# SenseEnable.net
KiCad netlist of a schematic drawn in Altium Designer
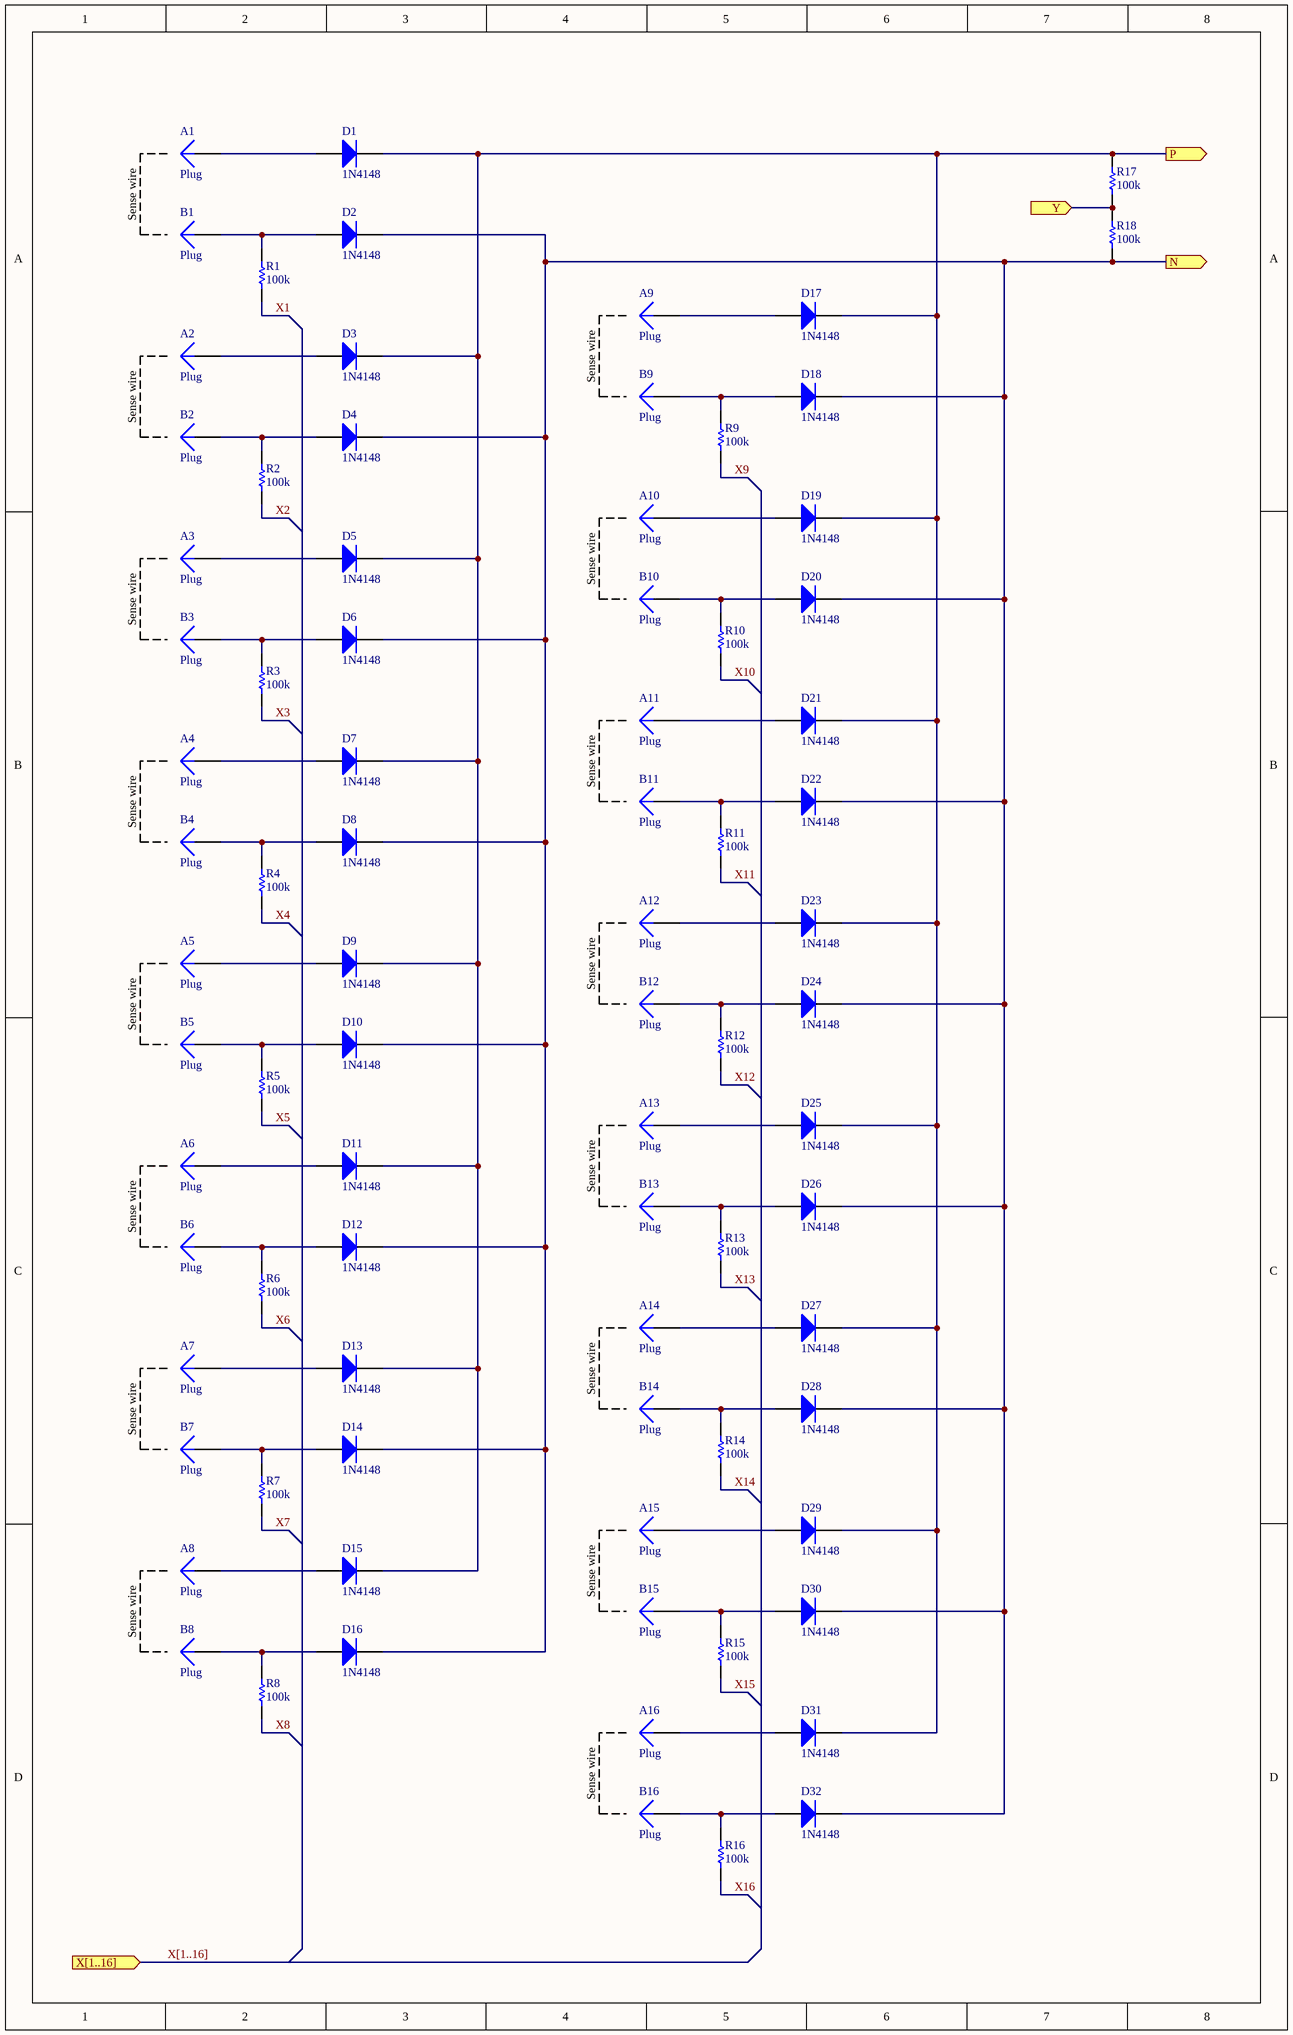
[diagram p0: SenseEnable.SchDoc]

(export (version "E")
  (design (tool "Eeschema 10.0.6"))
  (components
    (comp (ref "A1")
      (value "Plug")
      (footprint "PIN1")
      (fields (field (name "PUBLISHER") "Altium Limited"))
      (libsource (lib "Miscellaneous Connectors") (part "Plug"))
    )
    (comp (ref "A2")
      (value "Plug")
      (footprint "PIN1")
      (fields (field (name "PUBLISHER") "Altium Limited"))
      (libsource (lib "Miscellaneous Connectors") (part "Plug"))
    )
    (comp (ref "A3")
      (value "Plug")
      (footprint "PIN1")
      (fields (field (name "PUBLISHER") "Altium Limited"))
      (libsource (lib "Miscellaneous Connectors") (part "Plug"))
    )
    (comp (ref "A4")
      (value "Plug")
      (footprint "PIN1")
      (fields (field (name "PUBLISHER") "Altium Limited"))
      (libsource (lib "Miscellaneous Connectors") (part "Plug"))
    )
    (comp (ref "A5")
      (value "Plug")
      (footprint "PIN1")
      (fields (field (name "PUBLISHER") "Altium Limited"))
      (libsource (lib "Miscellaneous Connectors") (part "Plug"))
    )
    (comp (ref "A6")
      (value "Plug")
      (footprint "PIN1")
      (fields (field (name "PUBLISHER") "Altium Limited"))
      (libsource (lib "Miscellaneous Connectors") (part "Plug"))
    )
    (comp (ref "A7")
      (value "Plug")
      (footprint "PIN1")
      (fields (field (name "PUBLISHER") "Altium Limited"))
      (libsource (lib "Miscellaneous Connectors") (part "Plug"))
    )
    (comp (ref "A8")
      (value "Plug")
      (footprint "PIN1")
      (fields (field (name "PUBLISHER") "Altium Limited"))
      (libsource (lib "Miscellaneous Connectors") (part "Plug"))
    )
    (comp (ref "A9")
      (value "Plug")
      (footprint "PIN1")
      (fields (field (name "PUBLISHER") "Altium Limited"))
      (libsource (lib "Miscellaneous Connectors") (part "Plug"))
    )
    (comp (ref "A10")
      (value "Plug")
      (footprint "PIN1")
      (fields (field (name "PUBLISHER") "Altium Limited"))
      (libsource (lib "Miscellaneous Connectors") (part "Plug"))
    )
    (comp (ref "A11")
      (value "Plug")
      (footprint "PIN1")
      (fields (field (name "PUBLISHER") "Altium Limited"))
      (libsource (lib "Miscellaneous Connectors") (part "Plug"))
    )
    (comp (ref "A12")
      (value "Plug")
      (footprint "PIN1")
      (fields (field (name "PUBLISHER") "Altium Limited"))
      (libsource (lib "Miscellaneous Connectors") (part "Plug"))
    )
    (comp (ref "A13")
      (value "Plug")
      (footprint "PIN1")
      (fields (field (name "PUBLISHER") "Altium Limited"))
      (libsource (lib "Miscellaneous Connectors") (part "Plug"))
    )
    (comp (ref "A14")
      (value "Plug")
      (footprint "PIN1")
      (fields (field (name "PUBLISHER") "Altium Limited"))
      (libsource (lib "Miscellaneous Connectors") (part "Plug"))
    )
    (comp (ref "A15")
      (value "Plug")
      (footprint "PIN1")
      (fields (field (name "PUBLISHER") "Altium Limited"))
      (libsource (lib "Miscellaneous Connectors") (part "Plug"))
    )
    (comp (ref "A16")
      (value "Plug")
      (footprint "PIN1")
      (fields (field (name "PUBLISHER") "Altium Limited"))
      (libsource (lib "Miscellaneous Connectors") (part "Plug"))
    )
    (comp (ref "B1")
      (value "Plug")
      (footprint "PIN1")
      (fields (field (name "PUBLISHER") "Altium Limited"))
      (libsource (lib "Miscellaneous Connectors") (part "Plug"))
    )
    (comp (ref "B2")
      (value "Plug")
      (footprint "PIN1")
      (fields (field (name "PUBLISHER") "Altium Limited"))
      (libsource (lib "Miscellaneous Connectors") (part "Plug"))
    )
    (comp (ref "B3")
      (value "Plug")
      (footprint "PIN1")
      (fields (field (name "PUBLISHER") "Altium Limited"))
      (libsource (lib "Miscellaneous Connectors") (part "Plug"))
    )
    (comp (ref "B4")
      (value "Plug")
      (footprint "PIN1")
      (fields (field (name "PUBLISHER") "Altium Limited"))
      (libsource (lib "Miscellaneous Connectors") (part "Plug"))
    )
    (comp (ref "B5")
      (value "Plug")
      (footprint "PIN1")
      (fields (field (name "PUBLISHER") "Altium Limited"))
      (libsource (lib "Miscellaneous Connectors") (part "Plug"))
    )
    (comp (ref "B6")
      (value "Plug")
      (footprint "PIN1")
      (fields (field (name "PUBLISHER") "Altium Limited"))
      (libsource (lib "Miscellaneous Connectors") (part "Plug"))
    )
    (comp (ref "B7")
      (value "Plug")
      (footprint "PIN1")
      (fields (field (name "PUBLISHER") "Altium Limited"))
      (libsource (lib "Miscellaneous Connectors") (part "Plug"))
    )
    (comp (ref "B8")
      (value "Plug")
      (footprint "PIN1")
      (fields (field (name "PUBLISHER") "Altium Limited"))
      (libsource (lib "Miscellaneous Connectors") (part "Plug"))
    )
    (comp (ref "B9")
      (value "Plug")
      (footprint "PIN1")
      (fields (field (name "PUBLISHER") "Altium Limited"))
      (libsource (lib "Miscellaneous Connectors") (part "Plug"))
    )
    (comp (ref "B10")
      (value "Plug")
      (footprint "PIN1")
      (fields (field (name "PUBLISHER") "Altium Limited"))
      (libsource (lib "Miscellaneous Connectors") (part "Plug"))
    )
    (comp (ref "B11")
      (value "Plug")
      (footprint "PIN1")
      (fields (field (name "PUBLISHER") "Altium Limited"))
      (libsource (lib "Miscellaneous Connectors") (part "Plug"))
    )
    (comp (ref "B12")
      (value "Plug")
      (footprint "PIN1")
      (fields (field (name "PUBLISHER") "Altium Limited"))
      (libsource (lib "Miscellaneous Connectors") (part "Plug"))
    )
    (comp (ref "B13")
      (value "Plug")
      (footprint "PIN1")
      (fields (field (name "PUBLISHER") "Altium Limited"))
      (libsource (lib "Miscellaneous Connectors") (part "Plug"))
    )
    (comp (ref "B14")
      (value "Plug")
      (footprint "PIN1")
      (fields (field (name "PUBLISHER") "Altium Limited"))
      (libsource (lib "Miscellaneous Connectors") (part "Plug"))
    )
    (comp (ref "B15")
      (value "Plug")
      (footprint "PIN1")
      (fields (field (name "PUBLISHER") "Altium Limited"))
      (libsource (lib "Miscellaneous Connectors") (part "Plug"))
    )
    (comp (ref "B16")
      (value "Plug")
      (footprint "PIN1")
      (fields (field (name "PUBLISHER") "Altium Limited"))
      (libsource (lib "Miscellaneous Connectors") (part "Plug"))
    )
    (comp (ref "D1")
      (value "1N4148")
      (footprint "DO-35")
      (description "High Conductance Fast Diode")
      (fields (field (name "PUBLISHER") "Altium Limited"))
      (libsource (lib "Miscellaneous Devices") (part "Diode 1N4148"))
    )
    (comp (ref "D2")
      (value "1N4148")
      (footprint "DO-35")
      (description "High Conductance Fast Diode")
      (fields (field (name "PUBLISHER") "Altium Limited"))
      (libsource (lib "Miscellaneous Devices") (part "Diode 1N4148"))
    )
    (comp (ref "D3")
      (value "1N4148")
      (footprint "DO-35")
      (description "High Conductance Fast Diode")
      (fields (field (name "PUBLISHER") "Altium Limited"))
      (libsource (lib "Miscellaneous Devices") (part "Diode 1N4148"))
    )
    (comp (ref "D4")
      (value "1N4148")
      (footprint "DO-35")
      (description "High Conductance Fast Diode")
      (fields (field (name "PUBLISHER") "Altium Limited"))
      (libsource (lib "Miscellaneous Devices") (part "Diode 1N4148"))
    )
    (comp (ref "D5")
      (value "1N4148")
      (footprint "DO-35")
      (description "High Conductance Fast Diode")
      (fields (field (name "PUBLISHER") "Altium Limited"))
      (libsource (lib "Miscellaneous Devices") (part "Diode 1N4148"))
    )
    (comp (ref "D6")
      (value "1N4148")
      (footprint "DO-35")
      (description "High Conductance Fast Diode")
      (fields (field (name "PUBLISHER") "Altium Limited"))
      (libsource (lib "Miscellaneous Devices") (part "Diode 1N4148"))
    )
    (comp (ref "D7")
      (value "1N4148")
      (footprint "DO-35")
      (description "High Conductance Fast Diode")
      (fields (field (name "PUBLISHER") "Altium Limited"))
      (libsource (lib "Miscellaneous Devices") (part "Diode 1N4148"))
    )
    (comp (ref "D8")
      (value "1N4148")
      (footprint "DO-35")
      (description "High Conductance Fast Diode")
      (fields (field (name "PUBLISHER") "Altium Limited"))
      (libsource (lib "Miscellaneous Devices") (part "Diode 1N4148"))
    )
    (comp (ref "D9")
      (value "1N4148")
      (footprint "DO-35")
      (description "High Conductance Fast Diode")
      (fields (field (name "PUBLISHER") "Altium Limited"))
      (libsource (lib "Miscellaneous Devices") (part "Diode 1N4148"))
    )
    (comp (ref "D10")
      (value "1N4148")
      (footprint "DO-35")
      (description "High Conductance Fast Diode")
      (fields (field (name "PUBLISHER") "Altium Limited"))
      (libsource (lib "Miscellaneous Devices") (part "Diode 1N4148"))
    )
    (comp (ref "D11")
      (value "1N4148")
      (footprint "DO-35")
      (description "High Conductance Fast Diode")
      (fields (field (name "PUBLISHER") "Altium Limited"))
      (libsource (lib "Miscellaneous Devices") (part "Diode 1N4148"))
    )
    (comp (ref "D12")
      (value "1N4148")
      (footprint "DO-35")
      (description "High Conductance Fast Diode")
      (fields (field (name "PUBLISHER") "Altium Limited"))
      (libsource (lib "Miscellaneous Devices") (part "Diode 1N4148"))
    )
    (comp (ref "D13")
      (value "1N4148")
      (footprint "DO-35")
      (description "High Conductance Fast Diode")
      (fields (field (name "PUBLISHER") "Altium Limited"))
      (libsource (lib "Miscellaneous Devices") (part "Diode 1N4148"))
    )
    (comp (ref "D14")
      (value "1N4148")
      (footprint "DO-35")
      (description "High Conductance Fast Diode")
      (fields (field (name "PUBLISHER") "Altium Limited"))
      (libsource (lib "Miscellaneous Devices") (part "Diode 1N4148"))
    )
    (comp (ref "D15")
      (value "1N4148")
      (footprint "DO-35")
      (description "High Conductance Fast Diode")
      (fields (field (name "PUBLISHER") "Altium Limited"))
      (libsource (lib "Miscellaneous Devices") (part "Diode 1N4148"))
    )
    (comp (ref "D16")
      (value "1N4148")
      (footprint "DO-35")
      (description "High Conductance Fast Diode")
      (fields (field (name "PUBLISHER") "Altium Limited"))
      (libsource (lib "Miscellaneous Devices") (part "Diode 1N4148"))
    )
    (comp (ref "D17")
      (value "1N4148")
      (footprint "DO-35")
      (description "High Conductance Fast Diode")
      (fields (field (name "PUBLISHER") "Altium Limited"))
      (libsource (lib "Miscellaneous Devices") (part "Diode 1N4148"))
    )
    (comp (ref "D18")
      (value "1N4148")
      (footprint "DO-35")
      (description "High Conductance Fast Diode")
      (fields (field (name "PUBLISHER") "Altium Limited"))
      (libsource (lib "Miscellaneous Devices") (part "Diode 1N4148"))
    )
    (comp (ref "D19")
      (value "1N4148")
      (footprint "DO-35")
      (description "High Conductance Fast Diode")
      (fields (field (name "PUBLISHER") "Altium Limited"))
      (libsource (lib "Miscellaneous Devices") (part "Diode 1N4148"))
    )
    (comp (ref "D20")
      (value "1N4148")
      (footprint "DO-35")
      (description "High Conductance Fast Diode")
      (fields (field (name "PUBLISHER") "Altium Limited"))
      (libsource (lib "Miscellaneous Devices") (part "Diode 1N4148"))
    )
    (comp (ref "D21")
      (value "1N4148")
      (footprint "DO-35")
      (description "High Conductance Fast Diode")
      (fields (field (name "PUBLISHER") "Altium Limited"))
      (libsource (lib "Miscellaneous Devices") (part "Diode 1N4148"))
    )
    (comp (ref "D22")
      (value "1N4148")
      (footprint "DO-35")
      (description "High Conductance Fast Diode")
      (fields (field (name "PUBLISHER") "Altium Limited"))
      (libsource (lib "Miscellaneous Devices") (part "Diode 1N4148"))
    )
    (comp (ref "D23")
      (value "1N4148")
      (footprint "DO-35")
      (description "High Conductance Fast Diode")
      (fields (field (name "PUBLISHER") "Altium Limited"))
      (libsource (lib "Miscellaneous Devices") (part "Diode 1N4148"))
    )
    (comp (ref "D24")
      (value "1N4148")
      (footprint "DO-35")
      (description "High Conductance Fast Diode")
      (fields (field (name "PUBLISHER") "Altium Limited"))
      (libsource (lib "Miscellaneous Devices") (part "Diode 1N4148"))
    )
    (comp (ref "D25")
      (value "1N4148")
      (footprint "DO-35")
      (description "High Conductance Fast Diode")
      (fields (field (name "PUBLISHER") "Altium Limited"))
      (libsource (lib "Miscellaneous Devices") (part "Diode 1N4148"))
    )
    (comp (ref "D26")
      (value "1N4148")
      (footprint "DO-35")
      (description "High Conductance Fast Diode")
      (fields (field (name "PUBLISHER") "Altium Limited"))
      (libsource (lib "Miscellaneous Devices") (part "Diode 1N4148"))
    )
    (comp (ref "D27")
      (value "1N4148")
      (footprint "DO-35")
      (description "High Conductance Fast Diode")
      (fields (field (name "PUBLISHER") "Altium Limited"))
      (libsource (lib "Miscellaneous Devices") (part "Diode 1N4148"))
    )
    (comp (ref "D28")
      (value "1N4148")
      (footprint "DO-35")
      (description "High Conductance Fast Diode")
      (fields (field (name "PUBLISHER") "Altium Limited"))
      (libsource (lib "Miscellaneous Devices") (part "Diode 1N4148"))
    )
    (comp (ref "D29")
      (value "1N4148")
      (footprint "DO-35")
      (description "High Conductance Fast Diode")
      (fields (field (name "PUBLISHER") "Altium Limited"))
      (libsource (lib "Miscellaneous Devices") (part "Diode 1N4148"))
    )
    (comp (ref "D30")
      (value "1N4148")
      (footprint "DO-35")
      (description "High Conductance Fast Diode")
      (fields (field (name "PUBLISHER") "Altium Limited"))
      (libsource (lib "Miscellaneous Devices") (part "Diode 1N4148"))
    )
    (comp (ref "D31")
      (value "1N4148")
      (footprint "DO-35")
      (description "High Conductance Fast Diode")
      (fields (field (name "PUBLISHER") "Altium Limited"))
      (libsource (lib "Miscellaneous Devices") (part "Diode 1N4148"))
    )
    (comp (ref "D32")
      (value "1N4148")
      (footprint "DO-35")
      (description "High Conductance Fast Diode")
      (fields (field (name "PUBLISHER") "Altium Limited"))
      (libsource (lib "Miscellaneous Devices") (part "Diode 1N4148"))
    )
    (comp (ref "R1")
      (value "100k")
      (footprint "AXIAL-0.3")
      (description "Resistor")
      (fields (field (name "PUBLISHER") "Altium Limited"))
      (libsource (lib "Miscellaneous Devices") (part "Res1"))
    )
    (comp (ref "R2")
      (value "100k")
      (footprint "AXIAL-0.3")
      (description "Resistor")
      (fields (field (name "PUBLISHER") "Altium Limited"))
      (libsource (lib "Miscellaneous Devices") (part "Res1"))
    )
    (comp (ref "R3")
      (value "100k")
      (footprint "AXIAL-0.3")
      (description "Resistor")
      (fields (field (name "PUBLISHER") "Altium Limited"))
      (libsource (lib "Miscellaneous Devices") (part "Res1"))
    )
    (comp (ref "R4")
      (value "100k")
      (footprint "AXIAL-0.3")
      (description "Resistor")
      (fields (field (name "PUBLISHER") "Altium Limited"))
      (libsource (lib "Miscellaneous Devices") (part "Res1"))
    )
    (comp (ref "R5")
      (value "100k")
      (footprint "AXIAL-0.3")
      (description "Resistor")
      (fields (field (name "PUBLISHER") "Altium Limited"))
      (libsource (lib "Miscellaneous Devices") (part "Res1"))
    )
    (comp (ref "R6")
      (value "100k")
      (footprint "AXIAL-0.3")
      (description "Resistor")
      (fields (field (name "PUBLISHER") "Altium Limited"))
      (libsource (lib "Miscellaneous Devices") (part "Res1"))
    )
    (comp (ref "R7")
      (value "100k")
      (footprint "AXIAL-0.3")
      (description "Resistor")
      (fields (field (name "PUBLISHER") "Altium Limited"))
      (libsource (lib "Miscellaneous Devices") (part "Res1"))
    )
    (comp (ref "R8")
      (value "100k")
      (footprint "AXIAL-0.3")
      (description "Resistor")
      (fields (field (name "PUBLISHER") "Altium Limited"))
      (libsource (lib "Miscellaneous Devices") (part "Res1"))
    )
    (comp (ref "R9")
      (value "100k")
      (footprint "AXIAL-0.3")
      (description "Resistor")
      (fields (field (name "PUBLISHER") "Altium Limited"))
      (libsource (lib "Miscellaneous Devices") (part "Res1"))
    )
    (comp (ref "R10")
      (value "100k")
      (footprint "AXIAL-0.3")
      (description "Resistor")
      (fields (field (name "PUBLISHER") "Altium Limited"))
      (libsource (lib "Miscellaneous Devices") (part "Res1"))
    )
    (comp (ref "R11")
      (value "100k")
      (footprint "AXIAL-0.3")
      (description "Resistor")
      (fields (field (name "PUBLISHER") "Altium Limited"))
      (libsource (lib "Miscellaneous Devices") (part "Res1"))
    )
    (comp (ref "R12")
      (value "100k")
      (footprint "AXIAL-0.3")
      (description "Resistor")
      (fields (field (name "PUBLISHER") "Altium Limited"))
      (libsource (lib "Miscellaneous Devices") (part "Res1"))
    )
    (comp (ref "R13")
      (value "100k")
      (footprint "AXIAL-0.3")
      (description "Resistor")
      (fields (field (name "PUBLISHER") "Altium Limited"))
      (libsource (lib "Miscellaneous Devices") (part "Res1"))
    )
    (comp (ref "R14")
      (value "100k")
      (footprint "AXIAL-0.3")
      (description "Resistor")
      (fields (field (name "PUBLISHER") "Altium Limited"))
      (libsource (lib "Miscellaneous Devices") (part "Res1"))
    )
    (comp (ref "R15")
      (value "100k")
      (footprint "AXIAL-0.3")
      (description "Resistor")
      (fields (field (name "PUBLISHER") "Altium Limited"))
      (libsource (lib "Miscellaneous Devices") (part "Res1"))
    )
    (comp (ref "R16")
      (value "100k")
      (footprint "AXIAL-0.3")
      (description "Resistor")
      (fields (field (name "PUBLISHER") "Altium Limited"))
      (libsource (lib "Miscellaneous Devices") (part "Res1"))
    )
    (comp (ref "R17")
      (value "100k")
      (footprint "AXIAL-0.3")
      (description "Resistor")
      (fields (field (name "PUBLISHER") "Altium Limited"))
      (libsource (lib "Miscellaneous Devices") (part "Res1"))
    )
    (comp (ref "R18")
      (value "100k")
      (footprint "AXIAL-0.3")
      (description "Resistor")
      (fields (field (name "PUBLISHER") "Altium Limited"))
      (libsource (lib "Miscellaneous Devices") (part "Res1"))
    )
  )
  (nets
    (net (code "1") (name "/N") (class "Default")
      (node (ref "D10") (pin "2") (pinfunction "K_2") (pintype "passive"))
      (node (ref "D12") (pin "2") (pinfunction "K_2") (pintype "passive"))
      (node (ref "D14") (pin "2") (pinfunction "K_2") (pintype "passive"))
      (node (ref "D16") (pin "2") (pinfunction "K_2") (pintype "passive"))
      (node (ref "D18") (pin "2") (pinfunction "K_2") (pintype "passive"))
      (node (ref "D2") (pin "2") (pinfunction "K_2") (pintype "passive"))
      (node (ref "D20") (pin "2") (pinfunction "K_2") (pintype "passive"))
      (node (ref "D22") (pin "2") (pinfunction "K_2") (pintype "passive"))
      (node (ref "D24") (pin "2") (pinfunction "K_2") (pintype "passive"))
      (node (ref "D26") (pin "2") (pinfunction "K_2") (pintype "passive"))
      (node (ref "D28") (pin "2") (pinfunction "K_2") (pintype "passive"))
      (node (ref "D30") (pin "2") (pinfunction "K_2") (pintype "passive"))
      (node (ref "D32") (pin "2") (pinfunction "K_2") (pintype "passive"))
      (node (ref "D4") (pin "2") (pinfunction "K_2") (pintype "passive"))
      (node (ref "D6") (pin "2") (pinfunction "K_2") (pintype "passive"))
      (node (ref "D8") (pin "2") (pinfunction "K_2") (pintype "passive"))
      (node (ref "R18") (pin "2") (pinfunction "2_2") (pintype "passive"))
    )
    (net (code "2") (name "/P") (class "Default")
      (node (ref "D1") (pin "2") (pinfunction "K_2") (pintype "passive"))
      (node (ref "D11") (pin "2") (pinfunction "K_2") (pintype "passive"))
      (node (ref "D13") (pin "2") (pinfunction "K_2") (pintype "passive"))
      (node (ref "D15") (pin "2") (pinfunction "K_2") (pintype "passive"))
      (node (ref "D17") (pin "2") (pinfunction "K_2") (pintype "passive"))
      (node (ref "D19") (pin "2") (pinfunction "K_2") (pintype "passive"))
      (node (ref "D21") (pin "2") (pinfunction "K_2") (pintype "passive"))
      (node (ref "D23") (pin "2") (pinfunction "K_2") (pintype "passive"))
      (node (ref "D25") (pin "2") (pinfunction "K_2") (pintype "passive"))
      (node (ref "D27") (pin "2") (pinfunction "K_2") (pintype "passive"))
      (node (ref "D29") (pin "2") (pinfunction "K_2") (pintype "passive"))
      (node (ref "D3") (pin "2") (pinfunction "K_2") (pintype "passive"))
      (node (ref "D31") (pin "2") (pinfunction "K_2") (pintype "passive"))
      (node (ref "D5") (pin "2") (pinfunction "K_2") (pintype "passive"))
      (node (ref "D7") (pin "2") (pinfunction "K_2") (pintype "passive"))
      (node (ref "D9") (pin "2") (pinfunction "K_2") (pintype "passive"))
      (node (ref "R17") (pin "1") (pinfunction "1_1") (pintype "passive"))
    )
    (net (code "3") (name "/X1") (class "Default")
      (node (ref "R1") (pin "2") (pinfunction "2_2") (pintype "passive"))
    )
    (net (code "4") (name "/X2") (class "Default")
      (node (ref "R2") (pin "2") (pinfunction "2_2") (pintype "passive"))
    )
    (net (code "5") (name "/X3") (class "Default")
      (node (ref "R3") (pin "2") (pinfunction "2_2") (pintype "passive"))
    )
    (net (code "6") (name "/X4") (class "Default")
      (node (ref "R4") (pin "2") (pinfunction "2_2") (pintype "passive"))
    )
    (net (code "7") (name "/X5") (class "Default")
      (node (ref "R5") (pin "2") (pinfunction "2_2") (pintype "passive"))
    )
    (net (code "8") (name "/X6") (class "Default")
      (node (ref "R6") (pin "2") (pinfunction "2_2") (pintype "passive"))
    )
    (net (code "9") (name "/X7") (class "Default")
      (node (ref "R7") (pin "2") (pinfunction "2_2") (pintype "passive"))
    )
    (net (code "10") (name "/X8") (class "Default")
      (node (ref "R8") (pin "2") (pinfunction "2_2") (pintype "passive"))
    )
    (net (code "11") (name "/X9") (class "Default")
      (node (ref "R9") (pin "2") (pinfunction "2_2") (pintype "passive"))
    )
    (net (code "12") (name "/X10") (class "Default")
      (node (ref "R10") (pin "2") (pinfunction "2_2") (pintype "passive"))
    )
    (net (code "13") (name "/X11") (class "Default")
      (node (ref "R11") (pin "2") (pinfunction "2_2") (pintype "passive"))
    )
    (net (code "14") (name "/X12") (class "Default")
      (node (ref "R12") (pin "2") (pinfunction "2_2") (pintype "passive"))
    )
    (net (code "15") (name "/X13") (class "Default")
      (node (ref "R13") (pin "2") (pinfunction "2_2") (pintype "passive"))
    )
    (net (code "16") (name "/X14") (class "Default")
      (node (ref "R14") (pin "2") (pinfunction "2_2") (pintype "passive"))
    )
    (net (code "17") (name "/X15") (class "Default")
      (node (ref "R15") (pin "2") (pinfunction "2_2") (pintype "passive"))
    )
    (net (code "18") (name "/X16") (class "Default")
      (node (ref "R16") (pin "2") (pinfunction "2_2") (pintype "passive"))
    )
    (net (code "20") (name "/Y") (class "Default")
      (node (ref "R17") (pin "2") (pinfunction "2_2") (pintype "passive"))
      (node (ref "R18") (pin "1") (pinfunction "1_1") (pintype "passive"))
    )
    (net (code "21") (name "Net-(D1-A)") (class "Default")
      (node (ref "A1") (pin "1") (pinfunction "1_1") (pintype "passive"))
      (node (ref "D1") (pin "1") (pinfunction "A_1") (pintype "passive"))
    )
    (net (code "22") (name "Net-(D2-A)") (class "Default")
      (node (ref "B1") (pin "1") (pinfunction "1_1") (pintype "passive"))
      (node (ref "D2") (pin "1") (pinfunction "A_1") (pintype "passive"))
      (node (ref "R1") (pin "1") (pinfunction "1_1") (pintype "passive"))
    )
    (net (code "23") (name "Net-(D3-A)") (class "Default")
      (node (ref "A2") (pin "1") (pinfunction "1_1") (pintype "passive"))
      (node (ref "D3") (pin "1") (pinfunction "A_1") (pintype "passive"))
    )
    (net (code "24") (name "Net-(D4-A)") (class "Default")
      (node (ref "B2") (pin "1") (pinfunction "1_1") (pintype "passive"))
      (node (ref "D4") (pin "1") (pinfunction "A_1") (pintype "passive"))
      (node (ref "R2") (pin "1") (pinfunction "1_1") (pintype "passive"))
    )
    (net (code "25") (name "Net-(D5-A)") (class "Default")
      (node (ref "A3") (pin "1") (pinfunction "1_1") (pintype "passive"))
      (node (ref "D5") (pin "1") (pinfunction "A_1") (pintype "passive"))
    )
    (net (code "26") (name "Net-(D6-A)") (class "Default")
      (node (ref "B3") (pin "1") (pinfunction "1_1") (pintype "passive"))
      (node (ref "D6") (pin "1") (pinfunction "A_1") (pintype "passive"))
      (node (ref "R3") (pin "1") (pinfunction "1_1") (pintype "passive"))
    )
    (net (code "27") (name "Net-(D7-A)") (class "Default")
      (node (ref "A4") (pin "1") (pinfunction "1_1") (pintype "passive"))
      (node (ref "D7") (pin "1") (pinfunction "A_1") (pintype "passive"))
    )
    (net (code "28") (name "Net-(D8-A)") (class "Default")
      (node (ref "B4") (pin "1") (pinfunction "1_1") (pintype "passive"))
      (node (ref "D8") (pin "1") (pinfunction "A_1") (pintype "passive"))
      (node (ref "R4") (pin "1") (pinfunction "1_1") (pintype "passive"))
    )
    (net (code "29") (name "Net-(D9-A)") (class "Default")
      (node (ref "A5") (pin "1") (pinfunction "1_1") (pintype "passive"))
      (node (ref "D9") (pin "1") (pinfunction "A_1") (pintype "passive"))
    )
    (net (code "30") (name "Net-(D10-A)") (class "Default")
      (node (ref "B5") (pin "1") (pinfunction "1_1") (pintype "passive"))
      (node (ref "D10") (pin "1") (pinfunction "A_1") (pintype "passive"))
      (node (ref "R5") (pin "1") (pinfunction "1_1") (pintype "passive"))
    )
    (net (code "31") (name "Net-(D11-A)") (class "Default")
      (node (ref "A6") (pin "1") (pinfunction "1_1") (pintype "passive"))
      (node (ref "D11") (pin "1") (pinfunction "A_1") (pintype "passive"))
    )
    (net (code "32") (name "Net-(D12-A)") (class "Default")
      (node (ref "B6") (pin "1") (pinfunction "1_1") (pintype "passive"))
      (node (ref "D12") (pin "1") (pinfunction "A_1") (pintype "passive"))
      (node (ref "R6") (pin "1") (pinfunction "1_1") (pintype "passive"))
    )
    (net (code "33") (name "Net-(D13-A)") (class "Default")
      (node (ref "A7") (pin "1") (pinfunction "1_1") (pintype "passive"))
      (node (ref "D13") (pin "1") (pinfunction "A_1") (pintype "passive"))
    )
    (net (code "34") (name "Net-(D14-A)") (class "Default")
      (node (ref "B7") (pin "1") (pinfunction "1_1") (pintype "passive"))
      (node (ref "D14") (pin "1") (pinfunction "A_1") (pintype "passive"))
      (node (ref "R7") (pin "1") (pinfunction "1_1") (pintype "passive"))
    )
    (net (code "35") (name "Net-(D15-A)") (class "Default")
      (node (ref "A8") (pin "1") (pinfunction "1_1") (pintype "passive"))
      (node (ref "D15") (pin "1") (pinfunction "A_1") (pintype "passive"))
    )
    (net (code "36") (name "Net-(D16-A)") (class "Default")
      (node (ref "B8") (pin "1") (pinfunction "1_1") (pintype "passive"))
      (node (ref "D16") (pin "1") (pinfunction "A_1") (pintype "passive"))
      (node (ref "R8") (pin "1") (pinfunction "1_1") (pintype "passive"))
    )
    (net (code "37") (name "Net-(D17-A)") (class "Default")
      (node (ref "A9") (pin "1") (pinfunction "1_1") (pintype "passive"))
      (node (ref "D17") (pin "1") (pinfunction "A_1") (pintype "passive"))
    )
    (net (code "38") (name "Net-(D18-A)") (class "Default")
      (node (ref "B9") (pin "1") (pinfunction "1_1") (pintype "passive"))
      (node (ref "D18") (pin "1") (pinfunction "A_1") (pintype "passive"))
      (node (ref "R9") (pin "1") (pinfunction "1_1") (pintype "passive"))
    )
    (net (code "39") (name "Net-(D19-A)") (class "Default")
      (node (ref "A10") (pin "1") (pinfunction "1_1") (pintype "passive"))
      (node (ref "D19") (pin "1") (pinfunction "A_1") (pintype "passive"))
    )
    (net (code "40") (name "Net-(D20-A)") (class "Default")
      (node (ref "B10") (pin "1") (pinfunction "1_1") (pintype "passive"))
      (node (ref "D20") (pin "1") (pinfunction "A_1") (pintype "passive"))
      (node (ref "R10") (pin "1") (pinfunction "1_1") (pintype "passive"))
    )
    (net (code "41") (name "Net-(D21-A)") (class "Default")
      (node (ref "A11") (pin "1") (pinfunction "1_1") (pintype "passive"))
      (node (ref "D21") (pin "1") (pinfunction "A_1") (pintype "passive"))
    )
    (net (code "42") (name "Net-(D22-A)") (class "Default")
      (node (ref "B11") (pin "1") (pinfunction "1_1") (pintype "passive"))
      (node (ref "D22") (pin "1") (pinfunction "A_1") (pintype "passive"))
      (node (ref "R11") (pin "1") (pinfunction "1_1") (pintype "passive"))
    )
    (net (code "43") (name "Net-(D23-A)") (class "Default")
      (node (ref "A12") (pin "1") (pinfunction "1_1") (pintype "passive"))
      (node (ref "D23") (pin "1") (pinfunction "A_1") (pintype "passive"))
    )
    (net (code "44") (name "Net-(D24-A)") (class "Default")
      (node (ref "B12") (pin "1") (pinfunction "1_1") (pintype "passive"))
      (node (ref "D24") (pin "1") (pinfunction "A_1") (pintype "passive"))
      (node (ref "R12") (pin "1") (pinfunction "1_1") (pintype "passive"))
    )
    (net (code "45") (name "Net-(D25-A)") (class "Default")
      (node (ref "A13") (pin "1") (pinfunction "1_1") (pintype "passive"))
      (node (ref "D25") (pin "1") (pinfunction "A_1") (pintype "passive"))
    )
    (net (code "46") (name "Net-(D26-A)") (class "Default")
      (node (ref "B13") (pin "1") (pinfunction "1_1") (pintype "passive"))
      (node (ref "D26") (pin "1") (pinfunction "A_1") (pintype "passive"))
      (node (ref "R13") (pin "1") (pinfunction "1_1") (pintype "passive"))
    )
    (net (code "47") (name "Net-(D27-A)") (class "Default")
      (node (ref "A14") (pin "1") (pinfunction "1_1") (pintype "passive"))
      (node (ref "D27") (pin "1") (pinfunction "A_1") (pintype "passive"))
    )
    (net (code "48") (name "Net-(D28-A)") (class "Default")
      (node (ref "B14") (pin "1") (pinfunction "1_1") (pintype "passive"))
      (node (ref "D28") (pin "1") (pinfunction "A_1") (pintype "passive"))
      (node (ref "R14") (pin "1") (pinfunction "1_1") (pintype "passive"))
    )
    (net (code "49") (name "Net-(D29-A)") (class "Default")
      (node (ref "A15") (pin "1") (pinfunction "1_1") (pintype "passive"))
      (node (ref "D29") (pin "1") (pinfunction "A_1") (pintype "passive"))
    )
    (net (code "50") (name "Net-(D30-A)") (class "Default")
      (node (ref "B15") (pin "1") (pinfunction "1_1") (pintype "passive"))
      (node (ref "D30") (pin "1") (pinfunction "A_1") (pintype "passive"))
      (node (ref "R15") (pin "1") (pinfunction "1_1") (pintype "passive"))
    )
    (net (code "51") (name "Net-(D31-A)") (class "Default")
      (node (ref "A16") (pin "1") (pinfunction "1_1") (pintype "passive"))
      (node (ref "D31") (pin "1") (pinfunction "A_1") (pintype "passive"))
    )
    (net (code "52") (name "Net-(D32-A)") (class "Default")
      (node (ref "B16") (pin "1") (pinfunction "1_1") (pintype "passive"))
      (node (ref "D32") (pin "1") (pinfunction "A_1") (pintype "passive"))
      (node (ref "R16") (pin "1") (pinfunction "1_1") (pintype "passive"))
    )
  )
)
